# TX_test.net
KiCad netlist of a schematic drawn in EAGLE
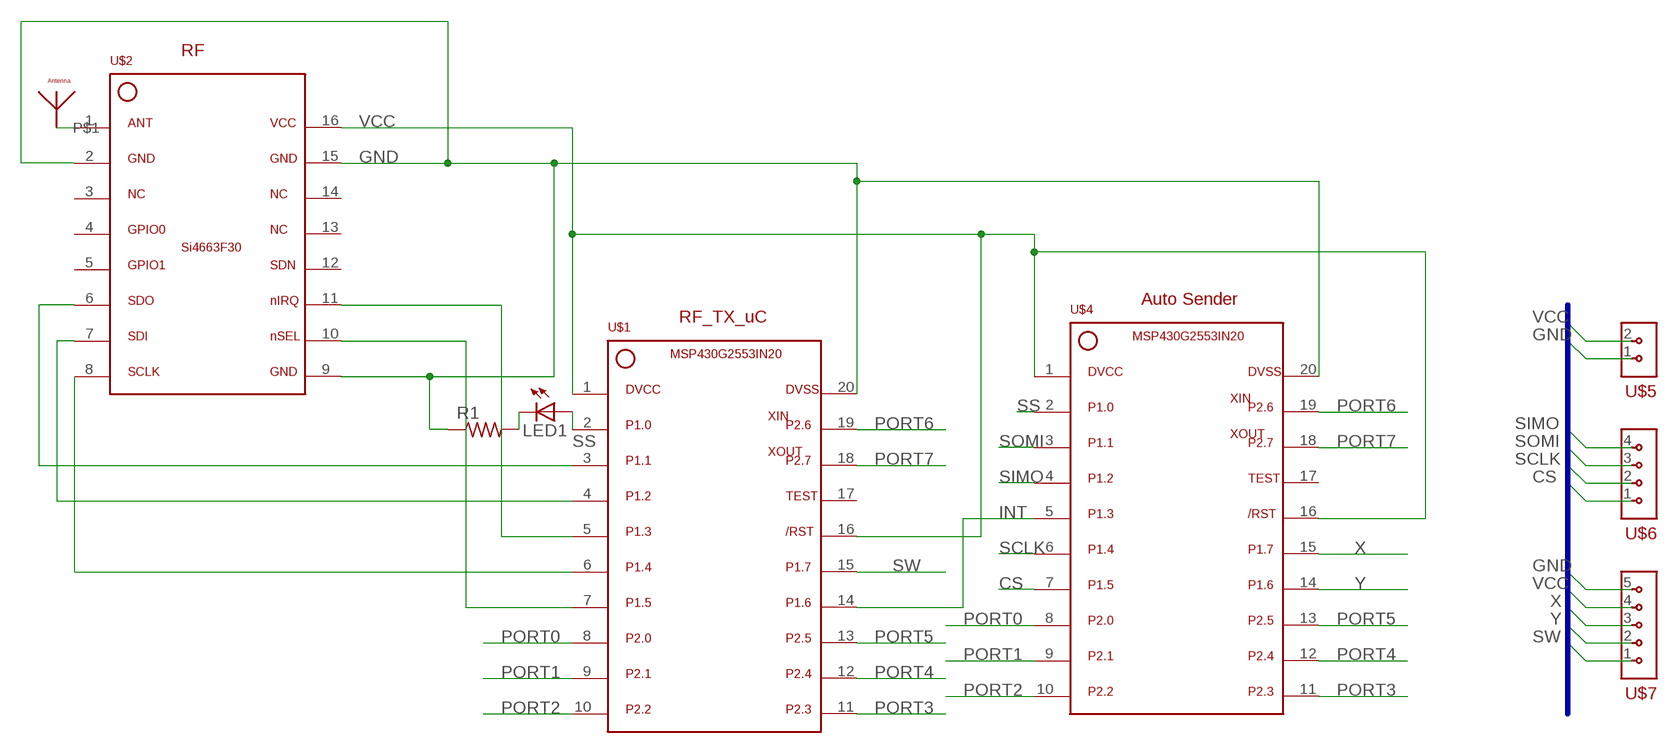
[diagram p0: schematic, sheet 1]

(export (version "E")
  (design (tool "Eeschema 10.0.6"))
  (components
    (comp (ref "LED1")
      (value "LED3MM")
      (footprint "eagle-import:LED3MM")
      (libsource (lib "eagle-import") (part "LED3MM"))
    )
    (comp (ref "R1")
      (value "R-US_0204/7")
      (footprint "eagle-import:0204_7")
      (libsource (lib "eagle-import") (part "R-US_0204/7"))
    )
    (comp (ref "U$1")
      (value "MSP430G2553IN20")
      (footprint "eagle-import:DIP762W53P254L2215H508Q20B")
      (libsource (lib "eagle-import") (part "MSP430G2553IN20"))
    )
    (comp (ref "U$2")
      (value "SI4663F30SI4663F30-3D")
      (footprint "eagle-import:INDCAV400P3800X2000X400-16N")
      (libsource (lib "eagle-import") (part "SI4663F30SI4663F30-3D"))
    )
    (comp (ref "U$3")
      (value "ANTENNA")
      (footprint "eagle-import:ANTENNA")
      (libsource (lib "eagle-import") (part "ANTENNA"))
    )
    (comp (ref "U$4")
      (value "MSP430G2553IN20")
      (footprint "eagle-import:DIP762W53P254L2215H508Q20B")
      (libsource (lib "eagle-import") (part "MSP430G2553IN20"))
    )
    (comp (ref "U$5")
      (value "H1X2")
      (footprint "eagle-import:HDRVR2W64P254_1X2_1016X508X254B")
      (libsource (lib "eagle-import") (part "H1X2"))
    )
    (comp (ref "U$6")
      (value "H1X4")
      (footprint "eagle-import:HDRRAR4W64P254_1X4_1016X736X556B")
      (libsource (lib "eagle-import") (part "H1X4"))
    )
    (comp (ref "U$7")
      (value "H1X5")
      (footprint "eagle-import:HDRRAR5W64P254_1X5_1016X736X556B")
      (libsource (lib "eagle-import") (part "H1X5"))
    )
  )
  (nets
    (net (code "1") (name "/CS") (class "Default")
      (node (ref "U$4") (pin "7") (pinfunction "P$7_7") (pintype "bidirectional"))
      (node (ref "U$6") (pin "1") (pinfunction "P$1_1") (pintype "bidirectional"))
    )
    (net (code "2") (name "/GND") (class "Default")
      (node (ref "R1") (pin "1") (pinfunction "1_1") (pintype "passive"))
      (node (ref "U$1") (pin "20") (pinfunction "P$20_20") (pintype "bidirectional"))
      (node (ref "U$2") (pin "15") (pinfunction "P$15_15") (pintype "bidirectional"))
      (node (ref "U$2") (pin "2") (pinfunction "P$2_2") (pintype "bidirectional"))
      (node (ref "U$2") (pin "9") (pinfunction "P$9_9") (pintype "bidirectional"))
      (node (ref "U$4") (pin "20") (pinfunction "P$20_20") (pintype "bidirectional"))
      (node (ref "U$5") (pin "1") (pinfunction "P$1_1") (pintype "bidirectional"))
      (node (ref "U$7") (pin "5") (pinfunction "P$5_5") (pintype "bidirectional"))
    )
    (net (code "3") (name "/INT") (class "Default")
      (node (ref "U$1") (pin "14") (pinfunction "P$14_14") (pintype "bidirectional"))
      (node (ref "U$4") (pin "5") (pinfunction "P$5_5") (pintype "bidirectional"))
    )
    (net (code "4") (name "/PORT0") (class "Default")
      (node (ref "U$1") (pin "8") (pinfunction "P$8_8") (pintype "bidirectional"))
      (node (ref "U$4") (pin "8") (pinfunction "P$8_8") (pintype "bidirectional"))
    )
    (net (code "5") (name "/PORT1") (class "Default")
      (node (ref "U$1") (pin "9") (pinfunction "P$9_9") (pintype "bidirectional"))
      (node (ref "U$4") (pin "9") (pinfunction "P$9_9") (pintype "bidirectional"))
    )
    (net (code "6") (name "/PORT2") (class "Default")
      (node (ref "U$1") (pin "10") (pinfunction "P$10_10") (pintype "bidirectional"))
      (node (ref "U$4") (pin "10") (pinfunction "P$10_10") (pintype "bidirectional"))
    )
    (net (code "7") (name "/PORT3") (class "Default")
      (node (ref "U$1") (pin "11") (pinfunction "P$11_11") (pintype "bidirectional"))
      (node (ref "U$4") (pin "11") (pinfunction "P$11_11") (pintype "bidirectional"))
    )
    (net (code "8") (name "/PORT4") (class "Default")
      (node (ref "U$1") (pin "12") (pinfunction "P$12_12") (pintype "bidirectional"))
      (node (ref "U$4") (pin "12") (pinfunction "P$12_12") (pintype "bidirectional"))
    )
    (net (code "9") (name "/PORT5") (class "Default")
      (node (ref "U$1") (pin "13") (pinfunction "P$13_13") (pintype "bidirectional"))
      (node (ref "U$4") (pin "13") (pinfunction "P$13_13") (pintype "bidirectional"))
    )
    (net (code "10") (name "/PORT6") (class "Default")
      (node (ref "U$1") (pin "19") (pinfunction "P$19_19") (pintype "bidirectional"))
      (node (ref "U$4") (pin "19") (pinfunction "P$19_19") (pintype "bidirectional"))
    )
    (net (code "11") (name "/PORT7") (class "Default")
      (node (ref "U$1") (pin "18") (pinfunction "P$18_18") (pintype "bidirectional"))
      (node (ref "U$4") (pin "18") (pinfunction "P$18_18") (pintype "bidirectional"))
    )
    (net (code "12") (name "/SCLK") (class "Default")
      (node (ref "U$4") (pin "6") (pinfunction "P$6_6") (pintype "bidirectional"))
      (node (ref "U$6") (pin "2") (pinfunction "P$2_2") (pintype "bidirectional"))
    )
    (net (code "13") (name "/SIMO") (class "Default")
      (node (ref "U$4") (pin "4") (pinfunction "P$4_4") (pintype "bidirectional"))
      (node (ref "U$6") (pin "4") (pinfunction "P$4_4") (pintype "bidirectional"))
    )
    (net (code "14") (name "/SOMI") (class "Default")
      (node (ref "U$4") (pin "3") (pinfunction "P$3_3") (pintype "bidirectional"))
      (node (ref "U$6") (pin "3") (pinfunction "P$3_3") (pintype "bidirectional"))
    )
    (net (code "15") (name "/SS") (class "Default")
      (node (ref "LED1") (pin "A") (pinfunction "A_A") (pintype "passive"))
      (node (ref "U$1") (pin "2") (pinfunction "P$2_2") (pintype "bidirectional"))
      (node (ref "U$4") (pin "2") (pinfunction "P$2_2") (pintype "bidirectional"))
    )
    (net (code "16") (name "/SW") (class "Default")
      (node (ref "U$1") (pin "15") (pinfunction "P$15_15") (pintype "bidirectional"))
      (node (ref "U$7") (pin "1") (pinfunction "P$1_1") (pintype "bidirectional"))
    )
    (net (code "17") (name "/VCC") (class "Default")
      (node (ref "U$1") (pin "1") (pinfunction "P$1_1") (pintype "bidirectional"))
      (node (ref "U$1") (pin "16") (pinfunction "P$16_16") (pintype "bidirectional"))
      (node (ref "U$2") (pin "16") (pinfunction "P$16_16") (pintype "bidirectional"))
      (node (ref "U$4") (pin "1") (pinfunction "P$1_1") (pintype "bidirectional"))
      (node (ref "U$4") (pin "16") (pinfunction "P$16_16") (pintype "bidirectional"))
      (node (ref "U$5") (pin "2") (pinfunction "P$2_2") (pintype "bidirectional"))
      (node (ref "U$7") (pin "4") (pinfunction "P$4_4") (pintype "bidirectional"))
    )
    (net (code "18") (name "/X") (class "Default")
      (node (ref "U$4") (pin "15") (pinfunction "P$15_15") (pintype "bidirectional"))
      (node (ref "U$7") (pin "3") (pinfunction "P$3_3") (pintype "bidirectional"))
    )
    (net (code "19") (name "/Y") (class "Default")
      (node (ref "U$4") (pin "14") (pinfunction "P$14_14") (pintype "bidirectional"))
      (node (ref "U$7") (pin "2") (pinfunction "P$2_2") (pintype "bidirectional"))
    )
    (net (code "20") (name "Net-(LED1-C)") (class "Default")
      (node (ref "LED1") (pin "K") (pinfunction "C_K") (pintype "passive"))
      (node (ref "R1") (pin "2") (pinfunction "2_2") (pintype "passive"))
    )
    (net (code "21") (name "Net-(U$1-P$3)") (class "Default")
      (node (ref "U$1") (pin "3") (pinfunction "P$3_3") (pintype "bidirectional"))
      (node (ref "U$2") (pin "6") (pinfunction "P$6_6") (pintype "bidirectional"))
    )
    (net (code "22") (name "Net-(U$1-P$4)") (class "Default")
      (node (ref "U$1") (pin "4") (pinfunction "P$4_4") (pintype "bidirectional"))
      (node (ref "U$2") (pin "7") (pinfunction "P$7_7") (pintype "bidirectional"))
    )
    (net (code "23") (name "Net-(U$1-P$5)") (class "Default")
      (node (ref "U$1") (pin "5") (pinfunction "P$5_5") (pintype "bidirectional"))
      (node (ref "U$2") (pin "11") (pinfunction "P$11_11") (pintype "bidirectional"))
    )
    (net (code "24") (name "Net-(U$1-P$6)") (class "Default")
      (node (ref "U$1") (pin "6") (pinfunction "P$6_6") (pintype "bidirectional"))
      (node (ref "U$2") (pin "8") (pinfunction "P$8_8") (pintype "bidirectional"))
    )
    (net (code "25") (name "Net-(U$1-P$7)") (class "Default")
      (node (ref "U$1") (pin "7") (pinfunction "P$7_7") (pintype "bidirectional"))
      (node (ref "U$2") (pin "10") (pinfunction "P$10_10") (pintype "bidirectional"))
    )
    (net (code "26") (name "Net-(U$2-P$1)") (class "Default")
      (node (ref "U$2") (pin "1") (pinfunction "P$1_1") (pintype "bidirectional"))
      (node (ref "U$3") (pin "P$1") (pinfunction "P$1_P$1") (pintype "bidirectional"))
    )
    (net (code "27") (name "unconnected-(U$1-P$17-Pad17)") (class "Default")
      (node (ref "U$1") (pin "17") (pinfunction "P$17_17") (pintype "bidirectional"))
    )
    (net (code "28") (name "unconnected-(U$2-P$3-Pad3)") (class "Default")
      (node (ref "U$2") (pin "3") (pinfunction "P$3_3") (pintype "bidirectional"))
    )
    (net (code "29") (name "unconnected-(U$2-P$4-Pad4)") (class "Default")
      (node (ref "U$2") (pin "4") (pinfunction "P$4_4") (pintype "bidirectional"))
    )
    (net (code "30") (name "unconnected-(U$2-P$5-Pad5)") (class "Default")
      (node (ref "U$2") (pin "5") (pinfunction "P$5_5") (pintype "bidirectional"))
    )
    (net (code "31") (name "unconnected-(U$2-P$12-Pad12)") (class "Default")
      (node (ref "U$2") (pin "12") (pinfunction "P$12_12") (pintype "bidirectional"))
    )
    (net (code "32") (name "unconnected-(U$2-P$13-Pad13)") (class "Default")
      (node (ref "U$2") (pin "13") (pinfunction "P$13_13") (pintype "bidirectional"))
    )
    (net (code "33") (name "unconnected-(U$2-P$14-Pad14)") (class "Default")
      (node (ref "U$2") (pin "14") (pinfunction "P$14_14") (pintype "bidirectional"))
    )
    (net (code "34") (name "unconnected-(U$4-P$17-Pad17)") (class "Default")
      (node (ref "U$4") (pin "17") (pinfunction "P$17_17") (pintype "bidirectional"))
    )
  )
)
